# LCD_Disp_AIR.net
KiCad netlist of a schematic drawn in EAGLE
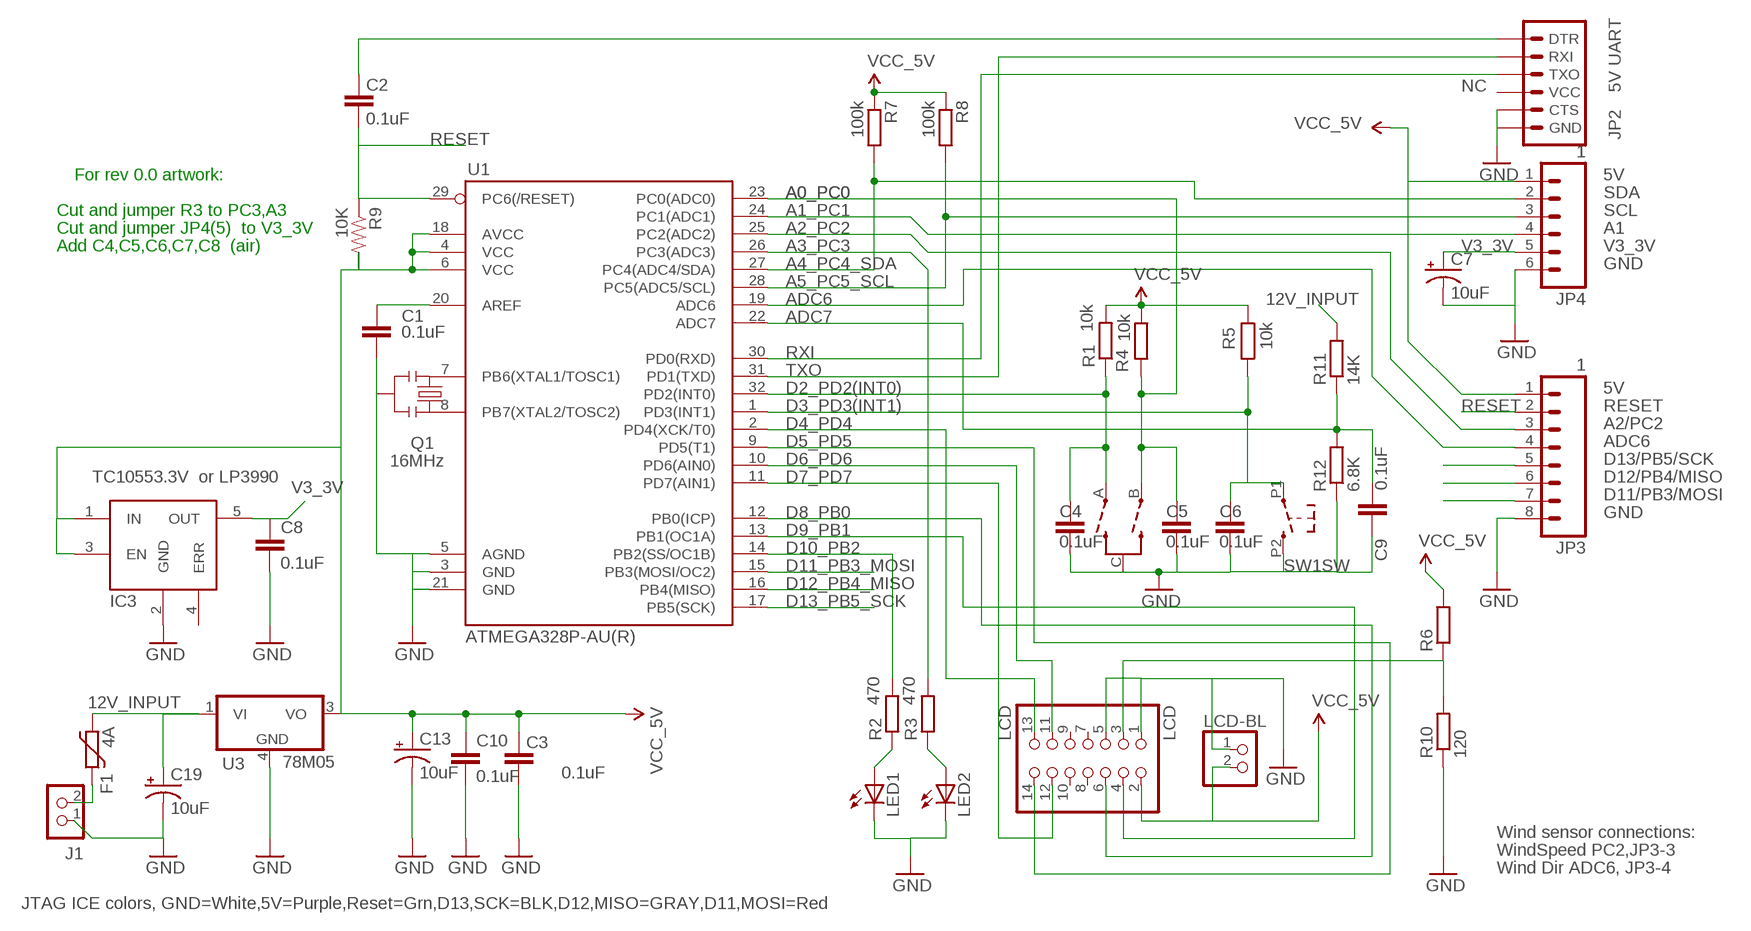
[diagram p0: schematic, sheet 1]

(export (version "E")
  (design (tool "Eeschema 10.0.6"))
  (components
    (comp (ref "C1")
      (value "0.1uF")
      (footprint "eagle-import:0805")
      (libsource (lib "eagle-import") (part "CAP0805"))
    )
    (comp (ref "C2")
      (value "0.1uF")
      (footprint "eagle-import:0805")
      (libsource (lib "eagle-import") (part "CAP0805"))
    )
    (comp (ref "C3")
      (value "0.1uF")
      (footprint "eagle-import:0805")
      (libsource (lib "eagle-import") (part "CAP0805"))
    )
    (comp (ref "C4")
      (value "0.1uF")
      (footprint "eagle-import:0805")
      (libsource (lib "eagle-import") (part "CAP0805"))
    )
    (comp (ref "C5")
      (value "0.1uF")
      (footprint "eagle-import:0805")
      (libsource (lib "eagle-import") (part "CAP0805"))
    )
    (comp (ref "C6")
      (value "0.1uF")
      (footprint "eagle-import:0805")
      (libsource (lib "eagle-import") (part "CAP0805"))
    )
    (comp (ref "C7")
      (value "10uF")
      (footprint "eagle-import:EIA3216")
      (libsource (lib "eagle-import") (part "CAP_POL1206"))
    )
    (comp (ref "C8")
      (value "0.1uF")
      (footprint "eagle-import:0805")
      (libsource (lib "eagle-import") (part "CAP0805"))
    )
    (comp (ref "C9")
      (value "0.1uF")
      (footprint "eagle-import:0805")
      (libsource (lib "eagle-import") (part "CAP0805"))
    )
    (comp (ref "C10")
      (value "0.1uF")
      (footprint "eagle-import:0805")
      (libsource (lib "eagle-import") (part "CAP0805"))
    )
    (comp (ref "C13")
      (value "10uF")
      (footprint "eagle-import:EIA3216")
      (libsource (lib "eagle-import") (part "CAP_POL1206"))
    )
    (comp (ref "C19")
      (value "10uF")
      (footprint "eagle-import:EIA7343")
      (libsource (lib "eagle-import") (part "CAP_POL7343"))
    )
    (comp (ref "F1")
      (value "4A")
      (footprint "eagle-import:PTC0805")
      (libsource (lib "eagle-import") (part "FUSE_PTC-0805"))
    )
    (comp (ref "IC3")
      (value "TC10553.3V")
      (footprint "eagle-import:SOT23-5")
      (libsource (lib "eagle-import") (part "TC10553.3V"))
    )
    (comp (ref "J1")
      (value "12V input")
      (footprint "eagle-import:M1X2")
      (libsource (lib "eagle-import") (part "CON_HEADER_1X02-PTH"))
    )
    (comp (ref "JP2")
      (value "5V UART")
      (footprint "eagle-import:1X06")
      (libsource (lib "eagle-import") (part "ARDUINO_SERIAL_PROGRAMPTH"))
    )
    (comp (ref "JP3")
      (value "1")
      (footprint "eagle-import:1X08")
      (libsource (lib "eagle-import") (part "M081X08"))
    )
    (comp (ref "JP4")
      (value "1")
      (footprint "eagle-import:1X06")
      (libsource (lib "eagle-import") (part "M06SIP"))
    )
    (comp (ref "LCD")
      (value "LCD")
      (footprint "eagle-import:2X07")
      (libsource (lib "eagle-import") (part "PINHD-2X7"))
    )
    (comp (ref "LCD-BL")
      (value "PINHD-1X2")
      (footprint "eagle-import:1X02")
      (libsource (lib "eagle-import") (part "PINHD-1X2"))
    )
    (comp (ref "LED1")
      (value "LED-5MM")
      (footprint "eagle-import:LED-5MM")
      (libsource (lib "eagle-import") (part "LED-5MM"))
    )
    (comp (ref "LED2")
      (value "LED-5MM")
      (footprint "eagle-import:LED-5MM")
      (libsource (lib "eagle-import") (part "LED-5MM"))
    )
    (comp (ref "Q1")
      (value "16MHz")
      (footprint "eagle-import:RESONATOR-SMD")
      (libsource (lib "eagle-import") (part "RESONATORSMD"))
    )
    (comp (ref "R1")
      (value "10k")
      (footprint "eagle-import:R603")
      (libsource (lib "eagle-import") (part "RESISTOR-0603"))
    )
    (comp (ref "R2")
      (value "470")
      (footprint "eagle-import:R603")
      (libsource (lib "eagle-import") (part "RESISTOR-0603"))
    )
    (comp (ref "R3")
      (value "470")
      (footprint "eagle-import:R603")
      (libsource (lib "eagle-import") (part "RESISTOR-0603"))
    )
    (comp (ref "R4")
      (value "10k")
      (footprint "eagle-import:R603")
      (libsource (lib "eagle-import") (part "RESISTOR-0603"))
    )
    (comp (ref "R5")
      (value "10k")
      (footprint "eagle-import:R603")
      (libsource (lib "eagle-import") (part "RESISTOR-0603"))
    )
    (comp (ref "R6")
      (value "RESISTOR-0603")
      (footprint "eagle-import:R603")
      (libsource (lib "eagle-import") (part "RESISTOR-0603"))
    )
    (comp (ref "R7")
      (value "100k")
      (footprint "eagle-import:R603")
      (libsource (lib "eagle-import") (part "RESISTOR-0603"))
    )
    (comp (ref "R8")
      (value "100k")
      (footprint "eagle-import:R603")
      (libsource (lib "eagle-import") (part "RESISTOR-0603"))
    )
    (comp (ref "R9")
      (value "10K")
      (footprint "eagle-import:0603")
      (libsource (lib "eagle-import") (part "RESISTOR0603"))
    )
    (comp (ref "R10")
      (value "120")
      (footprint "eagle-import:R603")
      (libsource (lib "eagle-import") (part "RESISTOR-0603"))
    )
    (comp (ref "R11")
      (value "14K")
      (footprint "eagle-import:R603")
      (libsource (lib "eagle-import") (part "RESISTOR-0603"))
    )
    (comp (ref "R12")
      (value "6.8K")
      (footprint "eagle-import:R603")
      (libsource (lib "eagle-import") (part "RESISTOR-0603"))
    )
    (comp (ref "SW1")
      (value "ENCODER_SW1-PEC12")
      (footprint "eagle-import:PEC12_INCREMENTAL_ENCODER")
      (libsource (lib "eagle-import") (part "ENCODER_SW1-PEC12"))
    )
    (comp (ref "U1")
      (value "ATMEGA328P-AU(R)")
      (footprint "eagle-import:TQFP32-08")
      (libsource (lib "eagle-import") (part "ATMEGA168"))
    )
    (comp (ref "U3")
      (value "78M05")
      (footprint "eagle-import:DPACK")
      (libsource (lib "eagle-import") (part "78MXXL"))
    )
  )
  (nets
    (net (code "1") (name "/12V_INPUT") (class "Default")
      (node (ref "C19") (pin "A") (pinfunction "+_A") (pintype "passive"))
      (node (ref "F1") (pin "2") (pinfunction "2_2") (pintype "passive"))
      (node (ref "R11") (pin "2") (pinfunction "2_2") (pintype "passive"))
      (node (ref "U3") (pin "1") (pinfunction "VI_1") (pintype "input"))
    )
    (net (code "2") (name "/A0_PC0") (class "Default")
      (node (ref "C5") (pin "2") (pinfunction "2_2") (pintype "passive"))
      (node (ref "R4") (pin "2") (pinfunction "2_2") (pintype "passive"))
      (node (ref "SW1") (pin "B") (pinfunction "B_B") (pintype "passive"))
      (node (ref "U1") (pin "23") (pinfunction "PC0(ADC0)_23") (pintype "bidirectional"))
    )
    (net (code "3") (name "/A1_PC1") (class "Default")
      (node (ref "JP4") (pin "4") (pinfunction "4_4") (pintype "passive"))
      (node (ref "U1") (pin "24") (pinfunction "PC1(ADC1)_24") (pintype "bidirectional"))
    )
    (net (code "4") (name "/A2_PC2") (class "Default")
      (node (ref "JP3") (pin "3") (pinfunction "3_3") (pintype "passive"))
      (node (ref "U1") (pin "25") (pinfunction "PC2(ADC2)_25") (pintype "bidirectional"))
    )
    (net (code "5") (name "/A3_PC3") (class "Default")
      (node (ref "R3") (pin "2") (pinfunction "2_2") (pintype "passive"))
      (node (ref "U1") (pin "26") (pinfunction "PC3(ADC3)_26") (pintype "bidirectional"))
    )
    (net (code "6") (name "/A4_PC4_SDA") (class "Default")
      (node (ref "JP4") (pin "2") (pinfunction "2_2") (pintype "passive"))
      (node (ref "R7") (pin "2") (pinfunction "2_2") (pintype "passive"))
      (node (ref "U1") (pin "27") (pinfunction "PC4(ADC4/SDA)_27") (pintype "bidirectional"))
    )
    (net (code "7") (name "/A5_PC5_SCL") (class "Default")
      (node (ref "JP4") (pin "3") (pinfunction "3_3") (pintype "passive"))
      (node (ref "R8") (pin "2") (pinfunction "2_2") (pintype "passive"))
      (node (ref "U1") (pin "28") (pinfunction "PC5(ADC5/SCL)_28") (pintype "bidirectional"))
    )
    (net (code "8") (name "/ADC6") (class "Default")
      (node (ref "JP3") (pin "4") (pinfunction "4_4") (pintype "passive"))
      (node (ref "U1") (pin "19") (pinfunction "ADC6_19") (pintype "bidirectional"))
    )
    (net (code "9") (name "/ADC7") (class "Default")
      (node (ref "C9") (pin "1") (pinfunction "1_1") (pintype "passive"))
      (node (ref "R11") (pin "1") (pinfunction "1_1") (pintype "passive"))
      (node (ref "R12") (pin "2") (pinfunction "2_2") (pintype "passive"))
      (node (ref "U1") (pin "22") (pinfunction "ADC7_22") (pintype "bidirectional"))
    )
    (net (code "10") (name "/D2_PD2(INT0)") (class "Default")
      (node (ref "C4") (pin "2") (pinfunction "2_2") (pintype "passive"))
      (node (ref "R1") (pin "1") (pinfunction "1_1") (pintype "passive"))
      (node (ref "SW1") (pin "A") (pinfunction "A_A") (pintype "passive"))
      (node (ref "U1") (pin "32") (pinfunction "PD2(INT0)_32") (pintype "bidirectional"))
    )
    (net (code "11") (name "/D3_PD3(INT1)") (class "Default")
      (node (ref "C6") (pin "2") (pinfunction "2_2") (pintype "passive"))
      (node (ref "R5") (pin "1") (pinfunction "1_1") (pintype "passive"))
      (node (ref "SW1") (pin "P1") (pinfunction "1_P1") (pintype "passive"))
      (node (ref "U1") (pin "1") (pinfunction "PD3(INT1)_1") (pintype "bidirectional"))
    )
    (net (code "12") (name "/D4_PD4") (class "Default")
      (node (ref "LCD") (pin "13") (pinfunction "13_13") (pintype "passive"))
      (node (ref "U1") (pin "2") (pinfunction "PD4(XCK/T0)_2") (pintype "bidirectional"))
    )
    (net (code "13") (name "/D5_PD5") (class "Default")
      (node (ref "LCD") (pin "14") (pinfunction "14_14") (pintype "passive"))
      (node (ref "U1") (pin "9") (pinfunction "PD5(T1)_9") (pintype "bidirectional"))
    )
    (net (code "14") (name "/D6_PD6") (class "Default")
      (node (ref "LCD") (pin "11") (pinfunction "11_11") (pintype "passive"))
      (node (ref "U1") (pin "10") (pinfunction "PD6(AIN0)_10") (pintype "bidirectional"))
    )
    (net (code "15") (name "/D7_PD7") (class "Default")
      (node (ref "LCD") (pin "12") (pinfunction "12_12") (pintype "passive"))
      (node (ref "U1") (pin "11") (pinfunction "PD7(AIN1)_11") (pintype "bidirectional"))
    )
    (net (code "16") (name "/D8_PB0") (class "Default")
      (node (ref "LCD") (pin "6") (pinfunction "6_6") (pintype "passive"))
      (node (ref "U1") (pin "12") (pinfunction "PB0(ICP)_12") (pintype "bidirectional"))
    )
    (net (code "17") (name "/D9_PB1") (class "Default")
      (node (ref "LCD") (pin "4") (pinfunction "4_4") (pintype "passive"))
      (node (ref "U1") (pin "13") (pinfunction "PB1(OC1A)_13") (pintype "bidirectional"))
    )
    (net (code "18") (name "/D10_PB2") (class "Default")
      (node (ref "R2") (pin "2") (pinfunction "2_2") (pintype "passive"))
      (node (ref "U1") (pin "14") (pinfunction "PB2(SS/OC1B)_14") (pintype "bidirectional"))
    )
    (net (code "19") (name "/D11_PB3_MOSI") (class "Default")
      (node (ref "JP3") (pin "7") (pinfunction "7_7") (pintype "passive"))
      (node (ref "U1") (pin "15") (pinfunction "PB3(MOSI/OC2)_15") (pintype "bidirectional"))
    )
    (net (code "20") (name "/D12_PB4_MISO") (class "Default")
      (node (ref "JP3") (pin "6") (pinfunction "6_6") (pintype "passive"))
      (node (ref "U1") (pin "16") (pinfunction "PB4(MISO)_16") (pintype "bidirectional"))
    )
    (net (code "21") (name "/D13_PB5_SCK") (class "Default")
      (node (ref "JP3") (pin "5") (pinfunction "5_5") (pintype "passive"))
      (node (ref "U1") (pin "17") (pinfunction "PB5(SCK)_17") (pintype "bidirectional"))
    )
    (net (code "22") (name "/RESET") (class "Default")
      (node (ref "C2") (pin "1") (pinfunction "1_1") (pintype "passive"))
      (node (ref "JP3") (pin "2") (pinfunction "2_2") (pintype "passive"))
      (node (ref "R9") (pin "1") (pinfunction "1_1") (pintype "passive"))
      (node (ref "U1") (pin "29") (pinfunction "PC6(/RESET)_29") (pintype "bidirectional"))
    )
    (net (code "23") (name "/RXI") (class "Default")
      (node (ref "JP2") (pin "3") (pinfunction "TXO_3") (pintype "passive"))
      (node (ref "U1") (pin "30") (pinfunction "PD0(RXD)_30") (pintype "bidirectional"))
    )
    (net (code "24") (name "/TXO") (class "Default")
      (node (ref "JP2") (pin "2") (pinfunction "RXI_2") (pintype "passive"))
      (node (ref "U1") (pin "31") (pinfunction "PD1(TXD)_31") (pintype "bidirectional"))
    )
    (net (code "25") (name "/V3_3V") (class "Default")
      (node (ref "C7") (pin "A") (pinfunction "+_A") (pintype "passive"))
      (node (ref "C8") (pin "1") (pinfunction "1_1") (pintype "passive"))
      (node (ref "IC3") (pin "5") (pinfunction "OUT_5") (pintype "power_in"))
      (node (ref "JP4") (pin "5") (pinfunction "5_5") (pintype "passive"))
    )
    (net (code "26") (name "GND") (class "Default")
      (node (ref "C1") (pin "1") (pinfunction "1_1") (pintype "passive"))
      (node (ref "C10") (pin "2") (pinfunction "2_2") (pintype "passive"))
      (node (ref "C13") (pin "C") (pinfunction "-_C") (pintype "passive"))
      (node (ref "C19") (pin "C") (pinfunction "-_C") (pintype "passive"))
      (node (ref "C3") (pin "1") (pinfunction "1_1") (pintype "passive"))
      (node (ref "C4") (pin "1") (pinfunction "1_1") (pintype "passive"))
      (node (ref "C5") (pin "1") (pinfunction "1_1") (pintype "passive"))
      (node (ref "C6") (pin "1") (pinfunction "1_1") (pintype "passive"))
      (node (ref "C7") (pin "C") (pinfunction "-_C") (pintype "passive"))
      (node (ref "C8") (pin "2") (pinfunction "2_2") (pintype "passive"))
      (node (ref "C9") (pin "2") (pinfunction "2_2") (pintype "passive"))
      (node (ref "IC3") (pin "2") (pinfunction "GND_2") (pintype "power_in"))
      (node (ref "J1") (pin "1") (pinfunction "1_1") (pintype "passive"))
      (node (ref "JP2") (pin "5") (pinfunction "CTS_5") (pintype "passive"))
      (node (ref "JP2") (pin "6") (pinfunction "GND_6") (pintype "passive"))
      (node (ref "JP3") (pin "8") (pinfunction "8_8") (pintype "passive"))
      (node (ref "JP4") (pin "6") (pinfunction "6_6") (pintype "passive"))
      (node (ref "LCD") (pin "1") (pinfunction "1_1") (pintype "passive"))
      (node (ref "LCD") (pin "5") (pinfunction "5_5") (pintype "passive"))
      (node (ref "LCD-BL") (pin "1") (pinfunction "1_1") (pintype "passive"))
      (node (ref "LED1") (pin "K") (pinfunction "C_K") (pintype "passive"))
      (node (ref "LED2") (pin "K") (pinfunction "C_K") (pintype "passive"))
      (node (ref "Q1") (pin "2") (pinfunction "2_2") (pintype "passive"))
      (node (ref "R10") (pin "1") (pinfunction "1_1") (pintype "passive"))
      (node (ref "R12") (pin "1") (pinfunction "1_1") (pintype "passive"))
      (node (ref "SW1") (pin "C") (pinfunction "C_C") (pintype "passive"))
      (node (ref "SW1") (pin "P2") (pinfunction "2_P2") (pintype "passive"))
      (node (ref "U1") (pin "21") (pinfunction "GND_21") (pintype "bidirectional"))
      (node (ref "U1") (pin "3") (pinfunction "GND_3") (pintype "bidirectional"))
      (node (ref "U1") (pin "5") (pinfunction "AGND_5") (pintype "bidirectional"))
      (node (ref "U3") (pin "4") (pinfunction "GND_4") (pintype "passive"))
    )
    (net (code "27") (name "Net-(F1-Pad1)") (class "Default")
      (node (ref "F1") (pin "1") (pinfunction "1_1") (pintype "passive"))
      (node (ref "J1") (pin "2") (pinfunction "2_2") (pintype "passive"))
    )
    (net (code "28") (name "Net-(JP2-DTR)") (class "Default")
      (node (ref "C2") (pin "2") (pinfunction "2_2") (pintype "passive"))
      (node (ref "JP2") (pin "1") (pinfunction "DTR_1") (pintype "passive"))
    )
    (net (code "29") (name "Net-(LCD-Pad3)") (class "Default")
      (node (ref "LCD") (pin "3") (pinfunction "3_3") (pintype "passive"))
      (node (ref "R10") (pin "2") (pinfunction "2_2") (pintype "passive"))
      (node (ref "R6") (pin "1") (pinfunction "1_1") (pintype "passive"))
    )
    (net (code "30") (name "Net-(LED1-PadA)") (class "Default")
      (node (ref "LED1") (pin "A") (pinfunction "A_A") (pintype "passive"))
      (node (ref "R2") (pin "1") (pinfunction "1_1") (pintype "passive"))
    )
    (net (code "31") (name "Net-(LED2-PadA)") (class "Default")
      (node (ref "LED2") (pin "A") (pinfunction "A_A") (pintype "passive"))
      (node (ref "R3") (pin "1") (pinfunction "1_1") (pintype "passive"))
    )
    (net (code "32") (name "Net-(U1-AREF)") (class "Default")
      (node (ref "C1") (pin "2") (pinfunction "2_2") (pintype "passive"))
      (node (ref "U1") (pin "20") (pinfunction "AREF_20") (pintype "bidirectional"))
    )
    (net (code "33") (name "Net-(U1-PB6(XTAL1{slash}TOSC1))") (class "Default")
      (node (ref "Q1") (pin "3") (pinfunction "3_3") (pintype "passive"))
      (node (ref "U1") (pin "7") (pinfunction "PB6(XTAL1/TOSC1)_7") (pintype "bidirectional"))
    )
    (net (code "34") (name "Net-(U1-PB7(XTAL2{slash}TOSC2))") (class "Default")
      (node (ref "Q1") (pin "1") (pinfunction "1_1") (pintype "passive"))
      (node (ref "U1") (pin "8") (pinfunction "PB7(XTAL2/TOSC2)_8") (pintype "bidirectional"))
    )
    (net (code "35") (name "VCC_5V") (class "Default")
      (node (ref "C10") (pin "1") (pinfunction "1_1") (pintype "passive"))
      (node (ref "C13") (pin "A") (pinfunction "+_A") (pintype "passive"))
      (node (ref "C3") (pin "2") (pinfunction "2_2") (pintype "passive"))
      (node (ref "IC3") (pin "1") (pinfunction "IN_1") (pintype "power_in"))
      (node (ref "IC3") (pin "3") (pinfunction "EN_3") (pintype "input"))
      (node (ref "JP3") (pin "1") (pinfunction "1_1") (pintype "passive"))
      (node (ref "JP4") (pin "1") (pinfunction "1_1") (pintype "passive"))
      (node (ref "LCD") (pin "2") (pinfunction "2_2") (pintype "passive"))
      (node (ref "LCD-BL") (pin "2") (pinfunction "2_2") (pintype "passive"))
      (node (ref "R1") (pin "2") (pinfunction "2_2") (pintype "passive"))
      (node (ref "R4") (pin "1") (pinfunction "1_1") (pintype "passive"))
      (node (ref "R5") (pin "2") (pinfunction "2_2") (pintype "passive"))
      (node (ref "R6") (pin "2") (pinfunction "2_2") (pintype "passive"))
      (node (ref "R7") (pin "1") (pinfunction "1_1") (pintype "passive"))
      (node (ref "R8") (pin "1") (pinfunction "1_1") (pintype "passive"))
      (node (ref "R9") (pin "2") (pinfunction "2_2") (pintype "passive"))
      (node (ref "U1") (pin "18") (pinfunction "AVCC_18") (pintype "bidirectional"))
      (node (ref "U1") (pin "4") (pinfunction "VCC_4") (pintype "bidirectional"))
      (node (ref "U1") (pin "6") (pinfunction "VCC_6") (pintype "bidirectional"))
      (node (ref "U3") (pin "3") (pinfunction "VO_3") (pintype "passive"))
    )
    (net (code "36") (name "unconnected-(IC3-ERR-Pad4)") (class "Default")
      (node (ref "IC3") (pin "4") (pinfunction "ERR_4") (pintype "output"))
    )
    (net (code "37") (name "unconnected-(JP2-VCC-Pad4)") (class "Default")
      (node (ref "JP2") (pin "4") (pinfunction "VCC_4") (pintype "passive"))
    )
    (net (code "38") (name "unconnected-(LCD-Pad7)") (class "Default")
      (node (ref "LCD") (pin "7") (pinfunction "7_7") (pintype "passive"))
    )
    (net (code "39") (name "unconnected-(LCD-Pad8)") (class "Default")
      (node (ref "LCD") (pin "8") (pinfunction "8_8") (pintype "passive"))
    )
    (net (code "40") (name "unconnected-(LCD-Pad9)") (class "Default")
      (node (ref "LCD") (pin "9") (pinfunction "9_9") (pintype "passive"))
    )
    (net (code "41") (name "unconnected-(LCD-Pad10)") (class "Default")
      (node (ref "LCD") (pin "10") (pinfunction "10_10") (pintype "passive"))
    )
  )
)
